# serverboard.net
KiCad netlist of a schematic drawn in Altium Designer
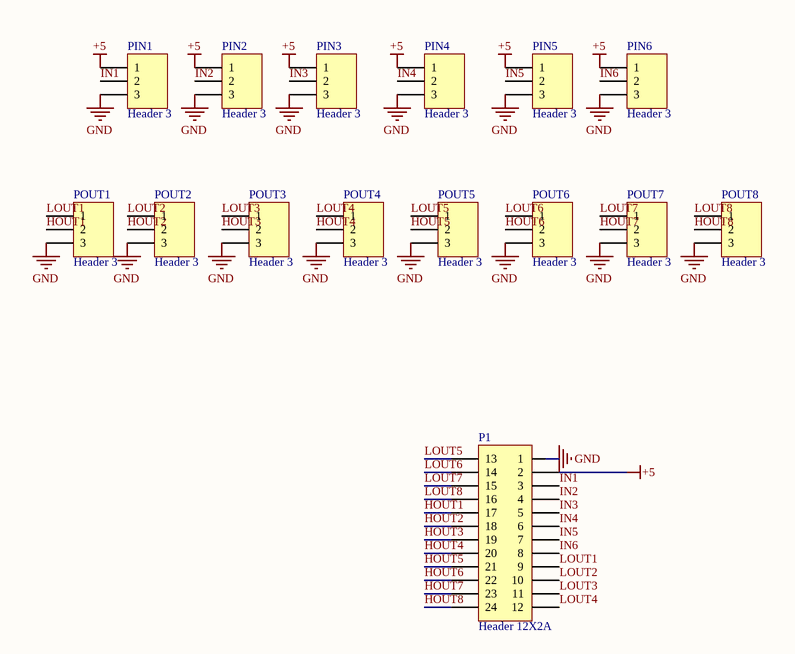
[diagram p0: serverboard.SchDoc]

(export (version "E")
  (design (tool "Eeschema 10.0.6"))
  (components
    (comp (ref "P1")
      (value "Header 12X2A")
      (footprint "HDR2X12_CEN")
      (description "Header, 12-Pin, Dual row")
      (fields (field (name "PUBLISHER") "Altium Limited"))
      (libsource (lib "Miscellaneous Connectors") (part "Header 12X2A"))
    )
    (comp (ref "PIN1")
      (value "Header 3")
      (footprint "HDR1X3")
      (description "Header, 3-Pin")
      (fields (field (name "PUBLISHER") "Altium Limited"))
      (libsource (lib "Miscellaneous Connectors") (part "Header 3"))
    )
    (comp (ref "PIN2")
      (value "Header 3")
      (footprint "HDR1X3")
      (description "Header, 3-Pin")
      (fields (field (name "PUBLISHER") "Altium Limited"))
      (libsource (lib "Miscellaneous Connectors") (part "Header 3"))
    )
    (comp (ref "PIN3")
      (value "Header 3")
      (footprint "HDR1X3")
      (description "Header, 3-Pin")
      (fields (field (name "PUBLISHER") "Altium Limited"))
      (libsource (lib "Miscellaneous Connectors") (part "Header 3"))
    )
    (comp (ref "PIN4")
      (value "Header 3")
      (footprint "HDR1X3")
      (description "Header, 3-Pin")
      (fields (field (name "PUBLISHER") "Altium Limited"))
      (libsource (lib "Miscellaneous Connectors") (part "Header 3"))
    )
    (comp (ref "PIN5")
      (value "Header 3")
      (footprint "HDR1X3")
      (description "Header, 3-Pin")
      (fields (field (name "PUBLISHER") "Altium Limited"))
      (libsource (lib "Miscellaneous Connectors") (part "Header 3"))
    )
    (comp (ref "PIN6")
      (value "Header 3")
      (footprint "HDR1X3")
      (description "Header, 3-Pin")
      (fields (field (name "PUBLISHER") "Altium Limited"))
      (libsource (lib "Miscellaneous Connectors") (part "Header 3"))
    )
    (comp (ref "POUT1")
      (value "Header 3")
      (footprint "HDR1X3")
      (description "Header, 3-Pin")
      (fields (field (name "PUBLISHER") "Altium Limited"))
      (libsource (lib "Miscellaneous Connectors") (part "Header 3"))
    )
    (comp (ref "POUT2")
      (value "Header 3")
      (footprint "HDR1X3")
      (description "Header, 3-Pin")
      (fields (field (name "PUBLISHER") "Altium Limited"))
      (libsource (lib "Miscellaneous Connectors") (part "Header 3"))
    )
    (comp (ref "POUT3")
      (value "Header 3")
      (footprint "HDR1X3")
      (description "Header, 3-Pin")
      (fields (field (name "PUBLISHER") "Altium Limited"))
      (libsource (lib "Miscellaneous Connectors") (part "Header 3"))
    )
    (comp (ref "POUT4")
      (value "Header 3")
      (footprint "HDR1X3")
      (description "Header, 3-Pin")
      (fields (field (name "PUBLISHER") "Altium Limited"))
      (libsource (lib "Miscellaneous Connectors") (part "Header 3"))
    )
    (comp (ref "POUT5")
      (value "Header 3")
      (footprint "HDR1X3")
      (description "Header, 3-Pin")
      (fields (field (name "PUBLISHER") "Altium Limited"))
      (libsource (lib "Miscellaneous Connectors") (part "Header 3"))
    )
    (comp (ref "POUT6")
      (value "Header 3")
      (footprint "HDR1X3")
      (description "Header, 3-Pin")
      (fields (field (name "PUBLISHER") "Altium Limited"))
      (libsource (lib "Miscellaneous Connectors") (part "Header 3"))
    )
    (comp (ref "POUT7")
      (value "Header 3")
      (footprint "HDR1X3")
      (description "Header, 3-Pin")
      (fields (field (name "PUBLISHER") "Altium Limited"))
      (libsource (lib "Miscellaneous Connectors") (part "Header 3"))
    )
    (comp (ref "POUT8")
      (value "Header 3")
      (footprint "HDR1X3")
      (description "Header, 3-Pin")
      (fields (field (name "PUBLISHER") "Altium Limited"))
      (libsource (lib "Miscellaneous Connectors") (part "Header 3"))
    )
  )
  (nets
    (net (code "1") (name "+5") (class "Default")
      (node (ref "P1") (pin "2") (pinfunction "2_2") (pintype "passive"))
      (node (ref "PIN1") (pin "1") (pinfunction "1_1") (pintype "passive"))
      (node (ref "PIN2") (pin "1") (pinfunction "1_1") (pintype "passive"))
      (node (ref "PIN3") (pin "1") (pinfunction "1_1") (pintype "passive"))
      (node (ref "PIN4") (pin "1") (pinfunction "1_1") (pintype "passive"))
      (node (ref "PIN5") (pin "1") (pinfunction "1_1") (pintype "passive"))
      (node (ref "PIN6") (pin "1") (pinfunction "1_1") (pintype "passive"))
    )
    (net (code "2") (name "/HOUT1") (class "Default")
      (node (ref "P1") (pin "17") (pinfunction "17_17") (pintype "passive"))
      (node (ref "POUT1") (pin "2") (pinfunction "2_2") (pintype "passive"))
    )
    (net (code "3") (name "/HOUT2") (class "Default")
      (node (ref "P1") (pin "18") (pinfunction "18_18") (pintype "passive"))
      (node (ref "POUT2") (pin "2") (pinfunction "2_2") (pintype "passive"))
    )
    (net (code "4") (name "/HOUT3") (class "Default")
      (node (ref "P1") (pin "19") (pinfunction "19_19") (pintype "passive"))
      (node (ref "POUT3") (pin "2") (pinfunction "2_2") (pintype "passive"))
    )
    (net (code "5") (name "/HOUT4") (class "Default")
      (node (ref "P1") (pin "20") (pinfunction "20_20") (pintype "passive"))
      (node (ref "POUT4") (pin "2") (pinfunction "2_2") (pintype "passive"))
    )
    (net (code "6") (name "/HOUT5") (class "Default")
      (node (ref "P1") (pin "21") (pinfunction "21_21") (pintype "passive"))
      (node (ref "POUT5") (pin "2") (pinfunction "2_2") (pintype "passive"))
    )
    (net (code "7") (name "/HOUT6") (class "Default")
      (node (ref "P1") (pin "22") (pinfunction "22_22") (pintype "passive"))
      (node (ref "POUT6") (pin "2") (pinfunction "2_2") (pintype "passive"))
    )
    (net (code "8") (name "/HOUT7") (class "Default")
      (node (ref "P1") (pin "23") (pinfunction "23_23") (pintype "passive"))
      (node (ref "POUT7") (pin "2") (pinfunction "2_2") (pintype "passive"))
    )
    (net (code "9") (name "/HOUT8") (class "Default")
      (node (ref "P1") (pin "24") (pinfunction "24_24") (pintype "passive"))
      (node (ref "POUT8") (pin "2") (pinfunction "2_2") (pintype "passive"))
    )
    (net (code "10") (name "/IN1") (class "Default")
      (node (ref "P1") (pin "3") (pinfunction "3_3") (pintype "passive"))
      (node (ref "PIN1") (pin "2") (pinfunction "2_2") (pintype "passive"))
    )
    (net (code "11") (name "/IN2") (class "Default")
      (node (ref "P1") (pin "4") (pinfunction "4_4") (pintype "passive"))
      (node (ref "PIN2") (pin "2") (pinfunction "2_2") (pintype "passive"))
    )
    (net (code "12") (name "/IN3") (class "Default")
      (node (ref "P1") (pin "5") (pinfunction "5_5") (pintype "passive"))
      (node (ref "PIN3") (pin "2") (pinfunction "2_2") (pintype "passive"))
    )
    (net (code "13") (name "/IN4") (class "Default")
      (node (ref "P1") (pin "6") (pinfunction "6_6") (pintype "passive"))
      (node (ref "PIN4") (pin "2") (pinfunction "2_2") (pintype "passive"))
    )
    (net (code "14") (name "/IN5") (class "Default")
      (node (ref "P1") (pin "7") (pinfunction "7_7") (pintype "passive"))
      (node (ref "PIN5") (pin "2") (pinfunction "2_2") (pintype "passive"))
    )
    (net (code "15") (name "/IN6") (class "Default")
      (node (ref "P1") (pin "8") (pinfunction "8_8") (pintype "passive"))
      (node (ref "PIN6") (pin "2") (pinfunction "2_2") (pintype "passive"))
    )
    (net (code "16") (name "/LOUT1") (class "Default")
      (node (ref "P1") (pin "9") (pinfunction "9_9") (pintype "passive"))
      (node (ref "POUT1") (pin "1") (pinfunction "1_1") (pintype "passive"))
    )
    (net (code "17") (name "/LOUT2") (class "Default")
      (node (ref "P1") (pin "10") (pinfunction "10_10") (pintype "passive"))
      (node (ref "POUT2") (pin "1") (pinfunction "1_1") (pintype "passive"))
    )
    (net (code "18") (name "/LOUT3") (class "Default")
      (node (ref "P1") (pin "11") (pinfunction "11_11") (pintype "passive"))
      (node (ref "POUT3") (pin "1") (pinfunction "1_1") (pintype "passive"))
    )
    (net (code "19") (name "/LOUT4") (class "Default")
      (node (ref "P1") (pin "12") (pinfunction "12_12") (pintype "passive"))
      (node (ref "POUT4") (pin "1") (pinfunction "1_1") (pintype "passive"))
    )
    (net (code "20") (name "/LOUT5") (class "Default")
      (node (ref "P1") (pin "13") (pinfunction "13_13") (pintype "passive"))
      (node (ref "POUT5") (pin "1") (pinfunction "1_1") (pintype "passive"))
    )
    (net (code "21") (name "/LOUT6") (class "Default")
      (node (ref "P1") (pin "14") (pinfunction "14_14") (pintype "passive"))
      (node (ref "POUT6") (pin "1") (pinfunction "1_1") (pintype "passive"))
    )
    (net (code "22") (name "/LOUT7") (class "Default")
      (node (ref "P1") (pin "15") (pinfunction "15_15") (pintype "passive"))
      (node (ref "POUT7") (pin "1") (pinfunction "1_1") (pintype "passive"))
    )
    (net (code "23") (name "/LOUT8") (class "Default")
      (node (ref "P1") (pin "16") (pinfunction "16_16") (pintype "passive"))
      (node (ref "POUT8") (pin "1") (pinfunction "1_1") (pintype "passive"))
    )
    (net (code "24") (name "GND") (class "Default")
      (node (ref "P1") (pin "1") (pinfunction "1_1") (pintype "passive"))
      (node (ref "PIN1") (pin "3") (pinfunction "3_3") (pintype "passive"))
      (node (ref "PIN2") (pin "3") (pinfunction "3_3") (pintype "passive"))
      (node (ref "PIN3") (pin "3") (pinfunction "3_3") (pintype "passive"))
      (node (ref "PIN4") (pin "3") (pinfunction "3_3") (pintype "passive"))
      (node (ref "PIN5") (pin "3") (pinfunction "3_3") (pintype "passive"))
      (node (ref "PIN6") (pin "3") (pinfunction "3_3") (pintype "passive"))
      (node (ref "POUT1") (pin "3") (pinfunction "3_3") (pintype "passive"))
      (node (ref "POUT2") (pin "3") (pinfunction "3_3") (pintype "passive"))
      (node (ref "POUT3") (pin "3") (pinfunction "3_3") (pintype "passive"))
      (node (ref "POUT4") (pin "3") (pinfunction "3_3") (pintype "passive"))
      (node (ref "POUT5") (pin "3") (pinfunction "3_3") (pintype "passive"))
      (node (ref "POUT6") (pin "3") (pinfunction "3_3") (pintype "passive"))
      (node (ref "POUT7") (pin "3") (pinfunction "3_3") (pintype "passive"))
      (node (ref "POUT8") (pin "3") (pinfunction "3_3") (pintype "passive"))
    )
  )
)
